# i4screenhsmc.net
KiCad netlist of a schematic drawn in EAGLE
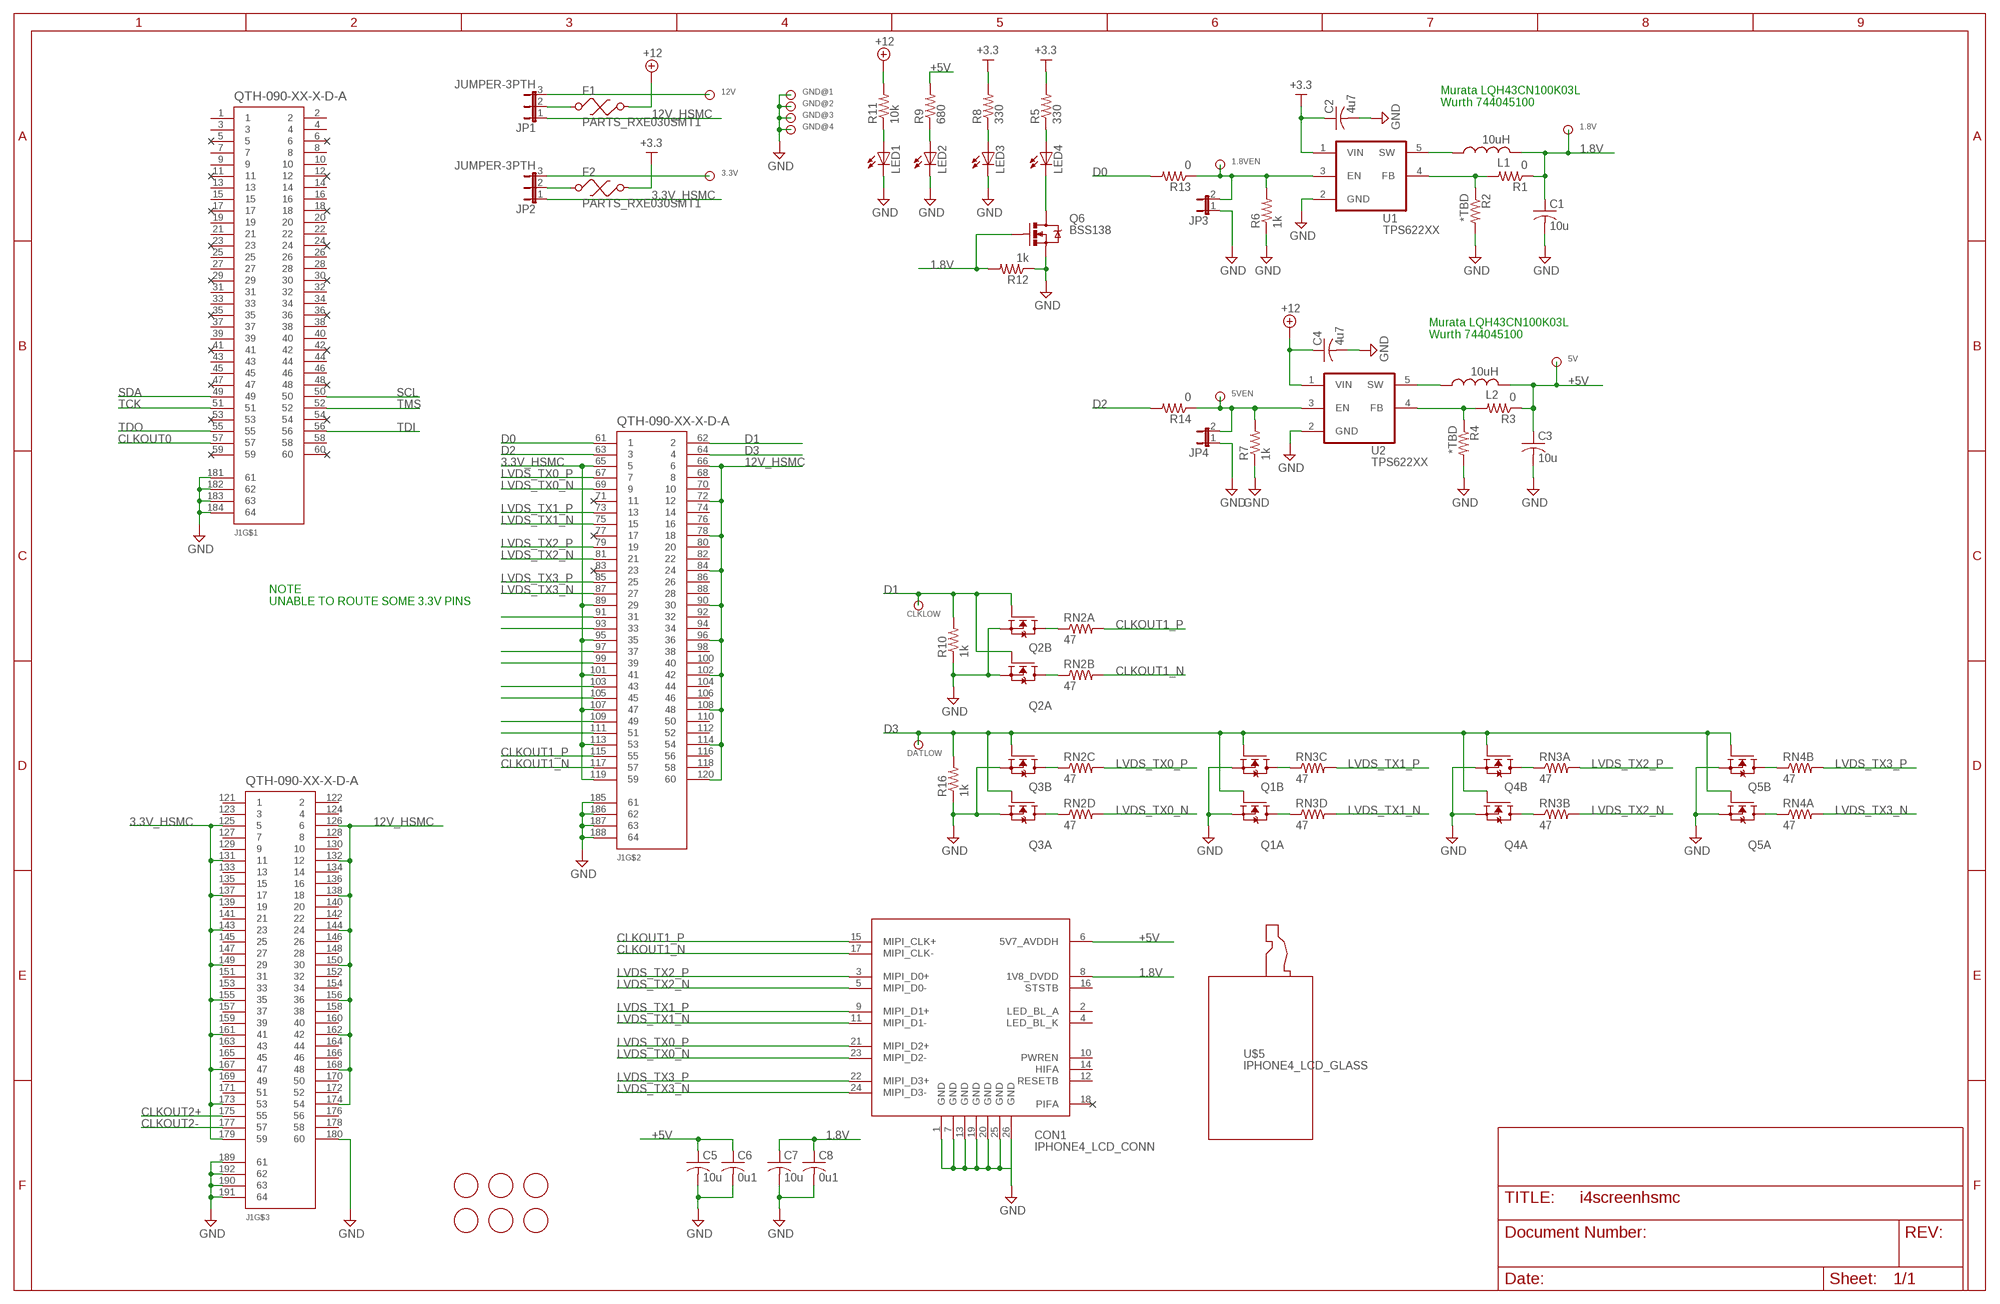
[diagram p0: schematic, sheet 1]

(export (version "E")
  (design (tool "Eeschema 10.0.6"))
  (components
    (comp (ref "1.8V")
      (value "TESTPOINTKEYSTONE_5015")
      (footprint "eagle-import:5015")
      (libsource (lib "eagle-import") (part "TESTPOINTKEYSTONE_5015"))
    )
    (comp (ref "1.8VEN")
      (value "TESTPOINTKEYSTONE_5016")
      (footprint "eagle-import:5016")
      (libsource (lib "eagle-import") (part "TESTPOINTKEYSTONE_5016"))
    )
    (comp (ref "3.3V")
      (value "TESTPOINTBANANA_JACK")
      (footprint "eagle-import:BANANA_JACK")
      (libsource (lib "eagle-import") (part "TESTPOINTBANANA_JACK"))
    )
    (comp (ref "5V")
      (value "TESTPOINTKEYSTONE_5015")
      (footprint "eagle-import:5015")
      (libsource (lib "eagle-import") (part "TESTPOINTKEYSTONE_5015"))
    )
    (comp (ref "5VEN")
      (value "TESTPOINTKEYSTONE_5016")
      (footprint "eagle-import:5016")
      (libsource (lib "eagle-import") (part "TESTPOINTKEYSTONE_5016"))
    )
    (comp (ref "12V")
      (value "TESTPOINTBANANA_JACK")
      (footprint "eagle-import:BANANA_JACK")
      (libsource (lib "eagle-import") (part "TESTPOINTBANANA_JACK"))
    )
    (comp (ref "C1")
      (value "10u")
      (footprint "eagle-import:C0805")
      (libsource (lib "eagle-import") (part "C-USC0805"))
    )
    (comp (ref "C2")
      (value "4u7")
      (footprint "eagle-import:C0805")
      (libsource (lib "eagle-import") (part "C-USC0805"))
    )
    (comp (ref "C3")
      (value "10u")
      (footprint "eagle-import:C0805")
      (libsource (lib "eagle-import") (part "C-USC0805"))
    )
    (comp (ref "C4")
      (value "4u7")
      (footprint "eagle-import:C0805")
      (libsource (lib "eagle-import") (part "C-USC0805"))
    )
    (comp (ref "C5")
      (value "10u")
      (footprint "eagle-import:C0805")
      (libsource (lib "eagle-import") (part "C-USC0805"))
    )
    (comp (ref "C6")
      (value "0u1")
      (footprint "eagle-import:C0805")
      (libsource (lib "eagle-import") (part "C-USC0805"))
    )
    (comp (ref "C7")
      (value "10u")
      (footprint "eagle-import:C0805")
      (libsource (lib "eagle-import") (part "C-USC0805"))
    )
    (comp (ref "C8")
      (value "0u1")
      (footprint "eagle-import:C0805")
      (libsource (lib "eagle-import") (part "C-USC0805"))
    )
    (comp (ref "CLKLOW")
      (value "TESTPOINTKEYSTONE_5016")
      (footprint "eagle-import:5016")
      (libsource (lib "eagle-import") (part "TESTPOINTKEYSTONE_5016"))
    )
    (comp (ref "CON1")
      (value "IPHONE4_LCD_CONN")
      (footprint "eagle-import:AXE4E26124")
      (libsource (lib "eagle-import") (part "IPHONE4_LCD_CONN"))
    )
    (comp (ref "DATLOW")
      (value "TESTPOINTKEYSTONE_5016")
      (footprint "eagle-import:5016")
      (libsource (lib "eagle-import") (part "TESTPOINTKEYSTONE_5016"))
    )
    (comp (ref "F1")
      (value "PARTS_RXE030SMT1")
      (footprint "eagle-import:POLYSWITCH_SMTSMALL")
      (libsource (lib "eagle-import") (part "PARTS_RXE030SMT1"))
    )
    (comp (ref "F2")
      (value "PARTS_RXE030SMT1")
      (footprint "eagle-import:POLYSWITCH_SMTSMALL")
      (libsource (lib "eagle-import") (part "PARTS_RXE030SMT1"))
    )
    (comp (ref "GND@1")
      (value "TESTPOINTBANANA_JACK")
      (footprint "eagle-import:BANANA_JACK")
      (libsource (lib "eagle-import") (part "TESTPOINTBANANA_JACK"))
    )
    (comp (ref "GND@2")
      (value "TESTPOINTBANANA_JACK")
      (footprint "eagle-import:BANANA_JACK")
      (libsource (lib "eagle-import") (part "TESTPOINTBANANA_JACK"))
    )
    (comp (ref "GND@3")
      (value "TESTPOINTKEYSTONE_5015")
      (footprint "eagle-import:5015")
      (libsource (lib "eagle-import") (part "TESTPOINTKEYSTONE_5015"))
    )
    (comp (ref "GND@4")
      (value "TESTPOINTKEYSTONE_5015")
      (footprint "eagle-import:5015")
      (libsource (lib "eagle-import") (part "TESTPOINTKEYSTONE_5015"))
    )
    (comp (ref "J1")
      (value "QTH-090-XX-X-D-A")
      (footprint "eagle-import:QTH-090-XX-X-D-A")
      (libsource (lib "eagle-import") (part "QTH-090-XX-X-D-A"))
    )
    (comp (ref "JP1")
      (value "JUMPER-3PTH")
      (footprint "eagle-import:1X03")
      (libsource (lib "eagle-import") (part "JUMPER-3PTH"))
    )
    (comp (ref "JP2")
      (value "JUMPER-3PTH")
      (footprint "eagle-import:1X03")
      (libsource (lib "eagle-import") (part "JUMPER-3PTH"))
    )
    (comp (ref "JP3")
      (value "JUMPER-2PTH")
      (footprint "eagle-import:1X02")
      (libsource (lib "eagle-import") (part "JUMPER-2PTH"))
    )
    (comp (ref "JP4")
      (value "JUMPER-2PTH")
      (footprint "eagle-import:1X02")
      (libsource (lib "eagle-import") (part "JUMPER-2PTH"))
    )
    (comp (ref "L1")
      (value "10uH")
      (footprint "eagle-import:L1812")
      (libsource (lib "eagle-import") (part "L-USL1812"))
    )
    (comp (ref "L2")
      (value "10uH")
      (footprint "eagle-import:L1812")
      (libsource (lib "eagle-import") (part "L-USL1812"))
    )
    (comp (ref "LED1")
      (value "LEDCHIP-LED0805")
      (footprint "eagle-import:CHIP-LED0805")
      (libsource (lib "eagle-import") (part "LEDCHIP-LED0805"))
    )
    (comp (ref "LED2")
      (value "LEDCHIP-LED0805")
      (footprint "eagle-import:CHIP-LED0805")
      (libsource (lib "eagle-import") (part "LEDCHIP-LED0805"))
    )
    (comp (ref "LED3")
      (value "LEDCHIP-LED0805")
      (footprint "eagle-import:CHIP-LED0805")
      (libsource (lib "eagle-import") (part "LEDCHIP-LED0805"))
    )
    (comp (ref "LED4")
      (value "LEDCHIP-LED0805")
      (footprint "eagle-import:CHIP-LED0805")
      (libsource (lib "eagle-import") (part "LEDCHIP-LED0805"))
    )
    (comp (ref "Q1")
      (value "2N7002SC70-6")
      (footprint "eagle-import:SC70-6")
      (libsource (lib "eagle-import") (part "2N7002SC70-6"))
    )
    (comp (ref "Q2")
      (value "2N7002SC70-6")
      (footprint "eagle-import:SC70-6")
      (libsource (lib "eagle-import") (part "2N7002SC70-6"))
    )
    (comp (ref "Q3")
      (value "2N7002SC70-6")
      (footprint "eagle-import:SC70-6")
      (libsource (lib "eagle-import") (part "2N7002SC70-6"))
    )
    (comp (ref "Q4")
      (value "2N7002SC70-6")
      (footprint "eagle-import:SC70-6")
      (libsource (lib "eagle-import") (part "2N7002SC70-6"))
    )
    (comp (ref "Q5")
      (value "2N7002SC70-6")
      (footprint "eagle-import:SC70-6")
      (libsource (lib "eagle-import") (part "2N7002SC70-6"))
    )
    (comp (ref "Q6")
      (value "BSS138")
      (footprint "eagle-import:SOT23-3")
      (libsource (lib "eagle-import") (part "MOSFET-NCHANNELSMD"))
    )
    (comp (ref "R1")
      (value "0")
      (footprint "eagle-import:R0805")
      (libsource (lib "eagle-import") (part "R-US_R0805"))
    )
    (comp (ref "R2")
      (value "*TBD")
      (footprint "eagle-import:R0805")
      (libsource (lib "eagle-import") (part "R-US_R0805"))
    )
    (comp (ref "R3")
      (value "0")
      (footprint "eagle-import:R0805")
      (libsource (lib "eagle-import") (part "R-US_R0805"))
    )
    (comp (ref "R4")
      (value "*TBD")
      (footprint "eagle-import:R0805")
      (libsource (lib "eagle-import") (part "R-US_R0805"))
    )
    (comp (ref "R5")
      (value "330")
      (footprint "eagle-import:R0805")
      (libsource (lib "eagle-import") (part "R-US_R0805"))
    )
    (comp (ref "R6")
      (value "1k")
      (footprint "eagle-import:R0805")
      (libsource (lib "eagle-import") (part "R-US_R0805"))
    )
    (comp (ref "R7")
      (value "1k")
      (footprint "eagle-import:R0805")
      (libsource (lib "eagle-import") (part "R-US_R0805"))
    )
    (comp (ref "R8")
      (value "330")
      (footprint "eagle-import:R0805")
      (libsource (lib "eagle-import") (part "R-US_R0805"))
    )
    (comp (ref "R9")
      (value "680")
      (footprint "eagle-import:R0805")
      (libsource (lib "eagle-import") (part "R-US_R0805"))
    )
    (comp (ref "R10")
      (value "1k")
      (footprint "eagle-import:R0805")
      (libsource (lib "eagle-import") (part "R-US_R0805"))
    )
    (comp (ref "R11")
      (value "10k")
      (footprint "eagle-import:R0805")
      (libsource (lib "eagle-import") (part "R-US_R0805"))
    )
    (comp (ref "R12")
      (value "1k")
      (footprint "eagle-import:R0805")
      (libsource (lib "eagle-import") (part "R-US_R0805"))
    )
    (comp (ref "R13")
      (value "0")
      (footprint "eagle-import:R0805")
      (libsource (lib "eagle-import") (part "R-US_R0805"))
    )
    (comp (ref "R14")
      (value "0")
      (footprint "eagle-import:R0805")
      (libsource (lib "eagle-import") (part "R-US_R0805"))
    )
    (comp (ref "R16")
      (value "1k")
      (footprint "eagle-import:R0805")
      (libsource (lib "eagle-import") (part "R-US_R0805"))
    )
    (comp (ref "RN2")
      (value "47")
      (footprint "eagle-import:2008")
      (libsource (lib "eagle-import") (part "RES_NETWORK0805"))
    )
    (comp (ref "RN3")
      (value "47")
      (footprint "eagle-import:2008")
      (libsource (lib "eagle-import") (part "RES_NETWORK0805"))
    )
    (comp (ref "RN4")
      (value "47")
      (footprint "eagle-import:2008")
      (libsource (lib "eagle-import") (part "RES_NETWORK0805"))
    )
    (comp (ref "U$1")
      (value "MOUNTING_HOLE125")
      (footprint "eagle-import:HOLE_MTG_125")
      (libsource (lib "eagle-import") (part "MOUNTING_HOLE125"))
    )
    (comp (ref "U$2")
      (value "MOUNTING_HOLE125")
      (footprint "eagle-import:HOLE_MTG_125")
      (libsource (lib "eagle-import") (part "MOUNTING_HOLE125"))
    )
    (comp (ref "U$3")
      (value "MOUNTING_HOLE125")
      (footprint "eagle-import:HOLE_MTG_125")
      (libsource (lib "eagle-import") (part "MOUNTING_HOLE125"))
    )
    (comp (ref "U$4")
      (value "MOUNTING_HOLE125")
      (footprint "eagle-import:HOLE_MTG_125")
      (libsource (lib "eagle-import") (part "MOUNTING_HOLE125"))
    )
    (comp (ref "U$5")
      (value "IPHONE4_LCD_GLASS")
      (footprint "eagle-import:IPHONE4_LCD")
      (libsource (lib "eagle-import") (part "IPHONE4_LCD_GLASS"))
    )
    (comp (ref "U$48")
      (value "MOUNTING_HOLE125")
      (footprint "eagle-import:HOLE_MTG_125")
      (libsource (lib "eagle-import") (part "MOUNTING_HOLE125"))
    )
    (comp (ref "U$49")
      (value "MOUNTING_HOLE125")
      (footprint "eagle-import:HOLE_MTG_125")
      (libsource (lib "eagle-import") (part "MOUNTING_HOLE125"))
    )
    (comp (ref "U1")
      (value "TPS622XX")
      (footprint "eagle-import:SOT23-5")
      (libsource (lib "eagle-import") (part "TPS622XX"))
    )
    (comp (ref "U2")
      (value "TPS622XX")
      (footprint "eagle-import:SOT23-5")
      (libsource (lib "eagle-import") (part "TPS622XX"))
    )
  )
  (nets
    (net (code "1") (name "+3.3") (class "Default")
      (node (ref "C2") (pin "1") (pinfunction "1_1") (pintype "passive"))
      (node (ref "F2") (pin "P$2") (pinfunction "2_P$2") (pintype "passive"))
      (node (ref "R5") (pin "2") (pinfunction "2_2") (pintype "passive"))
      (node (ref "R8") (pin "2") (pinfunction "2_2") (pintype "passive"))
      (node (ref "U1") (pin "1") (pinfunction "VIN_1") (pintype "passive"))
    )
    (net (code "2") (name "+12") (class "Default")
      (node (ref "C4") (pin "1") (pinfunction "1_1") (pintype "passive"))
      (node (ref "F1") (pin "P$2") (pinfunction "2_P$2") (pintype "passive"))
      (node (ref "R11") (pin "2") (pinfunction "2_2") (pintype "passive"))
      (node (ref "U2") (pin "1") (pinfunction "VIN_1") (pintype "passive"))
    )
    (net (code "3") (name "/+5V") (class "Default")
      (node (ref "5V") (pin "P$1") (pinfunction "1_P$1") (pintype "passive"))
      (node (ref "C3") (pin "1") (pinfunction "1_1") (pintype "passive"))
      (node (ref "C5") (pin "1") (pinfunction "1_1") (pintype "passive"))
      (node (ref "C6") (pin "1") (pinfunction "1_1") (pintype "passive"))
      (node (ref "CON1") (pin "6") (pinfunction "5V7_AVDDH_6") (pintype "power_in"))
      (node (ref "L2") (pin "2") (pinfunction "2_2") (pintype "passive"))
      (node (ref "R3") (pin "1") (pinfunction "1_1") (pintype "passive"))
      (node (ref "R9") (pin "2") (pinfunction "2_2") (pintype "passive"))
    )
    (net (code "4") (name "/1.8V") (class "Default")
      (node (ref "1.8V") (pin "P$1") (pinfunction "1_P$1") (pintype "passive"))
      (node (ref "C1") (pin "1") (pinfunction "1_1") (pintype "passive"))
      (node (ref "C7") (pin "1") (pinfunction "1_1") (pintype "passive"))
      (node (ref "C8") (pin "1") (pinfunction "1_1") (pintype "passive"))
      (node (ref "CON1") (pin "8") (pinfunction "1V8_DVDD_8") (pintype "power_in"))
      (node (ref "L1") (pin "2") (pinfunction "2_2") (pintype "passive"))
      (node (ref "Q6") (pin "1") (pinfunction "G_1") (pintype "passive"))
      (node (ref "R1") (pin "1") (pinfunction "1_1") (pintype "passive"))
      (node (ref "R12") (pin "2") (pinfunction "2_2") (pintype "passive"))
    )
    (net (code "5") (name "/3.3V_HSMC") (class "Default")
      (node (ref "J1") (pin "101") (pinfunction "41_101") (pintype "bidirectional"))
      (node (ref "J1") (pin "107") (pinfunction "47_107") (pintype "bidirectional"))
      (node (ref "J1") (pin "113") (pinfunction "53_113") (pintype "bidirectional"))
      (node (ref "J1") (pin "119") (pinfunction "59_119") (pintype "bidirectional"))
      (node (ref "J1") (pin "125") (pinfunction "5_125") (pintype "bidirectional"))
      (node (ref "J1") (pin "131") (pinfunction "11_131") (pintype "bidirectional"))
      (node (ref "J1") (pin "137") (pinfunction "17_137") (pintype "bidirectional"))
      (node (ref "J1") (pin "143") (pinfunction "23_143") (pintype "bidirectional"))
      (node (ref "J1") (pin "149") (pinfunction "29_149") (pintype "bidirectional"))
      (node (ref "J1") (pin "155") (pinfunction "35_155") (pintype "bidirectional"))
      (node (ref "J1") (pin "161") (pinfunction "41_161") (pintype "bidirectional"))
      (node (ref "J1") (pin "167") (pinfunction "47_167") (pintype "bidirectional"))
      (node (ref "J1") (pin "173") (pinfunction "53_173") (pintype "bidirectional"))
      (node (ref "J1") (pin "179") (pinfunction "59_179") (pintype "bidirectional"))
      (node (ref "J1") (pin "65") (pinfunction "5_65") (pintype "bidirectional"))
      (node (ref "J1") (pin "89") (pinfunction "29_89") (pintype "bidirectional"))
      (node (ref "J1") (pin "95") (pinfunction "35_95") (pintype "bidirectional"))
      (node (ref "JP2") (pin "1") (pinfunction "1_1") (pintype "passive"))
    )
    (net (code "6") (name "/12V_HSMC") (class "Default")
      (node (ref "J1") (pin "102") (pinfunction "42_102") (pintype "bidirectional"))
      (node (ref "J1") (pin "108") (pinfunction "48_108") (pintype "bidirectional"))
      (node (ref "J1") (pin "114") (pinfunction "54_114") (pintype "bidirectional"))
      (node (ref "J1") (pin "120") (pinfunction "60_120") (pintype "bidirectional"))
      (node (ref "J1") (pin "126") (pinfunction "6_126") (pintype "bidirectional"))
      (node (ref "J1") (pin "132") (pinfunction "12_132") (pintype "bidirectional"))
      (node (ref "J1") (pin "138") (pinfunction "18_138") (pintype "bidirectional"))
      (node (ref "J1") (pin "144") (pinfunction "24_144") (pintype "bidirectional"))
      (node (ref "J1") (pin "150") (pinfunction "30_150") (pintype "bidirectional"))
      (node (ref "J1") (pin "156") (pinfunction "36_156") (pintype "bidirectional"))
      (node (ref "J1") (pin "162") (pinfunction "42_162") (pintype "bidirectional"))
      (node (ref "J1") (pin "168") (pinfunction "48_168") (pintype "bidirectional"))
      (node (ref "J1") (pin "174") (pinfunction "54_174") (pintype "bidirectional"))
      (node (ref "J1") (pin "66") (pinfunction "6_66") (pintype "bidirectional"))
      (node (ref "J1") (pin "72") (pinfunction "12_72") (pintype "bidirectional"))
      (node (ref "J1") (pin "78") (pinfunction "18_78") (pintype "bidirectional"))
      (node (ref "J1") (pin "84") (pinfunction "24_84") (pintype "bidirectional"))
      (node (ref "J1") (pin "90") (pinfunction "30_90") (pintype "bidirectional"))
      (node (ref "J1") (pin "96") (pinfunction "36_96") (pintype "bidirectional"))
      (node (ref "JP1") (pin "1") (pinfunction "1_1") (pintype "passive"))
    )
    (net (code "7") (name "/CLKOUT0") (class "Default")
      (node (ref "J1") (pin "57") (pinfunction "57_57") (pintype "bidirectional"))
    )
    (net (code "8") (name "/CLKOUT1_N") (class "Default")
      (node (ref "CON1") (pin "17") (pinfunction "MIPI_CLK-_17") (pintype "input"))
      (node (ref "J1") (pin "117") (pinfunction "57_117") (pintype "bidirectional"))
      (node (ref "RN2") (pin "7") (pinfunction "2_7") (pintype "passive"))
    )
    (net (code "9") (name "/CLKOUT1_P") (class "Default")
      (node (ref "CON1") (pin "15") (pinfunction "MIPI_CLK+_15") (pintype "input"))
      (node (ref "J1") (pin "115") (pinfunction "55_115") (pintype "bidirectional"))
      (node (ref "RN2") (pin "8") (pinfunction "2_8") (pintype "passive"))
    )
    (net (code "10") (name "/CLKOUT2+") (class "Default")
      (node (ref "J1") (pin "175") (pinfunction "55_175") (pintype "bidirectional"))
    )
    (net (code "11") (name "/CLKOUT2-") (class "Default")
      (node (ref "J1") (pin "177") (pinfunction "57_177") (pintype "bidirectional"))
    )
    (net (code "12") (name "/D0") (class "Default")
      (node (ref "J1") (pin "61") (pinfunction "1_61") (pintype "bidirectional"))
      (node (ref "R13") (pin "2") (pinfunction "2_2") (pintype "passive"))
    )
    (net (code "13") (name "/D1") (class "Default")
      (node (ref "CLKLOW") (pin "P$1") (pinfunction "1_P$1") (pintype "passive"))
      (node (ref "J1") (pin "62") (pinfunction "2_62") (pintype "bidirectional"))
      (node (ref "Q2") (pin "2") (pinfunction "G_2") (pintype "passive"))
      (node (ref "Q2") (pin "5") (pinfunction "G_5") (pintype "passive"))
      (node (ref "R10") (pin "2") (pinfunction "2_2") (pintype "passive"))
    )
    (net (code "14") (name "/D2") (class "Default")
      (node (ref "J1") (pin "63") (pinfunction "3_63") (pintype "bidirectional"))
      (node (ref "R14") (pin "2") (pinfunction "2_2") (pintype "passive"))
    )
    (net (code "15") (name "/D3") (class "Default")
      (node (ref "DATLOW") (pin "P$1") (pinfunction "1_P$1") (pintype "passive"))
      (node (ref "J1") (pin "64") (pinfunction "4_64") (pintype "bidirectional"))
      (node (ref "Q1") (pin "2") (pinfunction "G_2") (pintype "passive"))
      (node (ref "Q1") (pin "5") (pinfunction "G_5") (pintype "passive"))
      (node (ref "Q3") (pin "2") (pinfunction "G_2") (pintype "passive"))
      (node (ref "Q3") (pin "5") (pinfunction "G_5") (pintype "passive"))
      (node (ref "Q4") (pin "2") (pinfunction "G_2") (pintype "passive"))
      (node (ref "Q4") (pin "5") (pinfunction "G_5") (pintype "passive"))
      (node (ref "Q5") (pin "2") (pinfunction "G_2") (pintype "passive"))
      (node (ref "Q5") (pin "5") (pinfunction "G_5") (pintype "passive"))
      (node (ref "R16") (pin "2") (pinfunction "2_2") (pintype "passive"))
    )
    (net (code "16") (name "/LVDS_TX0_N") (class "Default")
      (node (ref "CON1") (pin "23") (pinfunction "MIPI_D2-_23") (pintype "input"))
      (node (ref "J1") (pin "69") (pinfunction "9_69") (pintype "bidirectional"))
      (node (ref "RN2") (pin "5") (pinfunction "2_5") (pintype "passive"))
    )
    (net (code "17") (name "/LVDS_TX0_P") (class "Default")
      (node (ref "CON1") (pin "21") (pinfunction "MIPI_D2+_21") (pintype "input"))
      (node (ref "J1") (pin "67") (pinfunction "7_67") (pintype "bidirectional"))
      (node (ref "RN2") (pin "6") (pinfunction "2_6") (pintype "passive"))
    )
    (net (code "18") (name "/LVDS_TX1_N") (class "Default")
      (node (ref "CON1") (pin "11") (pinfunction "MIPI_D1-_11") (pintype "input"))
      (node (ref "J1") (pin "75") (pinfunction "15_75") (pintype "bidirectional"))
      (node (ref "RN3") (pin "5") (pinfunction "2_5") (pintype "passive"))
    )
    (net (code "19") (name "/LVDS_TX1_P") (class "Default")
      (node (ref "CON1") (pin "9") (pinfunction "MIPI_D1+_9") (pintype "input"))
      (node (ref "J1") (pin "73") (pinfunction "13_73") (pintype "bidirectional"))
      (node (ref "RN3") (pin "6") (pinfunction "2_6") (pintype "passive"))
    )
    (net (code "20") (name "/LVDS_TX2_N") (class "Default")
      (node (ref "CON1") (pin "5") (pinfunction "MIPI_D0-_5") (pintype "input"))
      (node (ref "J1") (pin "81") (pinfunction "21_81") (pintype "bidirectional"))
      (node (ref "RN3") (pin "7") (pinfunction "2_7") (pintype "passive"))
    )
    (net (code "21") (name "/LVDS_TX2_P") (class "Default")
      (node (ref "CON1") (pin "3") (pinfunction "MIPI_D0+_3") (pintype "input"))
      (node (ref "J1") (pin "79") (pinfunction "19_79") (pintype "bidirectional"))
      (node (ref "RN3") (pin "8") (pinfunction "2_8") (pintype "passive"))
    )
    (net (code "22") (name "/LVDS_TX3_N") (class "Default")
      (node (ref "CON1") (pin "24") (pinfunction "MIPI_D3-_24") (pintype "input"))
      (node (ref "J1") (pin "87") (pinfunction "27_87") (pintype "bidirectional"))
      (node (ref "RN4") (pin "8") (pinfunction "2_8") (pintype "passive"))
    )
    (net (code "23") (name "/LVDS_TX3_P") (class "Default")
      (node (ref "CON1") (pin "22") (pinfunction "MIPI_D3+_22") (pintype "input"))
      (node (ref "J1") (pin "85") (pinfunction "25_85") (pintype "bidirectional"))
      (node (ref "RN4") (pin "7") (pinfunction "2_7") (pintype "passive"))
    )
    (net (code "24") (name "/SCL") (class "Default")
      (node (ref "J1") (pin "50") (pinfunction "50_50") (pintype "bidirectional"))
    )
    (net (code "25") (name "/SDA") (class "Default")
      (node (ref "J1") (pin "49") (pinfunction "49_49") (pintype "bidirectional"))
    )
    (net (code "26") (name "/TCK") (class "Default")
      (node (ref "J1") (pin "51") (pinfunction "51_51") (pintype "bidirectional"))
    )
    (net (code "27") (name "/TDI") (class "Default")
      (node (ref "J1") (pin "56") (pinfunction "56_56") (pintype "bidirectional"))
    )
    (net (code "28") (name "/TDO") (class "Default")
      (node (ref "J1") (pin "55") (pinfunction "55_55") (pintype "bidirectional"))
    )
    (net (code "29") (name "/TMS") (class "Default")
      (node (ref "J1") (pin "52") (pinfunction "52_52") (pintype "bidirectional"))
    )
    (net (code "30") (name "GND") (class "Default")
      (node (ref "C1") (pin "2") (pinfunction "2_2") (pintype "passive"))
      (node (ref "C2") (pin "2") (pinfunction "2_2") (pintype "passive"))
      (node (ref "C3") (pin "2") (pinfunction "2_2") (pintype "passive"))
      (node (ref "C4") (pin "2") (pinfunction "2_2") (pintype "passive"))
      (node (ref "C5") (pin "2") (pinfunction "2_2") (pintype "passive"))
      (node (ref "C6") (pin "2") (pinfunction "2_2") (pintype "passive"))
      (node (ref "C7") (pin "2") (pinfunction "2_2") (pintype "passive"))
      (node (ref "C8") (pin "2") (pinfunction "2_2") (pintype "passive"))
      (node (ref "CON1") (pin "1") (pinfunction "GND_1") (pintype "power_in"))
      (node (ref "CON1") (pin "13") (pinfunction "GND_13") (pintype "power_in"))
      (node (ref "CON1") (pin "19") (pinfunction "GND_19") (pintype "power_in"))
      (node (ref "CON1") (pin "20") (pinfunction "GND_20") (pintype "power_in"))
      (node (ref "CON1") (pin "25") (pinfunction "GND_25") (pintype "power_in"))
      (node (ref "CON1") (pin "26") (pinfunction "GND_26") (pintype "power_in"))
      (node (ref "CON1") (pin "7") (pinfunction "GND_7") (pintype "power_in"))
      (node (ref "GND@1") (pin "1") (pinfunction "1_1") (pintype "passive"))
      (node (ref "GND@2") (pin "1") (pinfunction "1_1") (pintype "passive"))
      (node (ref "GND@3") (pin "P$1") (pinfunction "1_P$1") (pintype "passive"))
      (node (ref "GND@4") (pin "P$1") (pinfunction "1_P$1") (pintype "passive"))
      (node (ref "J1") (pin "180") (pinfunction "60_180") (pintype "bidirectional"))
      (node (ref "J1") (pin "181") (pinfunction "61_181") (pintype "power_in"))
      (node (ref "J1") (pin "182") (pinfunction "62_182") (pintype "power_in"))
      (node (ref "J1") (pin "183") (pinfunction "63_183") (pintype "power_in"))
      (node (ref "J1") (pin "184") (pinfunction "64_184") (pintype "power_in"))
      (node (ref "J1") (pin "185") (pinfunction "61_185") (pintype "power_in"))
      (node (ref "J1") (pin "186") (pinfunction "62_186") (pintype "power_in"))
      (node (ref "J1") (pin "187") (pinfunction "63_187") (pintype "power_in"))
      (node (ref "J1") (pin "188") (pinfunction "64_188") (pintype "power_in"))
      (node (ref "J1") (pin "189") (pinfunction "61_189") (pintype "power_in"))
      (node (ref "J1") (pin "190") (pinfunction "63_190") (pintype "power_in"))
      (node (ref "J1") (pin "191") (pinfunction "64_191") (pintype "power_in"))
      (node (ref "J1") (pin "192") (pinfunction "62_192") (pintype "power_in"))
      (node (ref "JP3") (pin "1") (pinfunction "1_1") (pintype "passive"))
      (node (ref "JP4") (pin "1") (pinfunction "1_1") (pintype "passive"))
      (node (ref "LED1") (pin "C") (pinfunction "C_C") (pintype "passive"))
      (node (ref "LED2") (pin "C") (pinfunction "C_C") (pintype "passive"))
      (node (ref "LED3") (pin "C") (pinfunction "C_C") (pintype "passive"))
      (node (ref "Q1") (pin "1") (pinfunction "S_1") (pintype "passive"))
      (node (ref "Q1") (pin "4") (pinfunction "S_4") (pintype "passive"))
      (node (ref "Q2") (pin "1") (pinfunction "S_1") (pintype "passive"))
      (node (ref "Q2") (pin "4") (pinfunction "S_4") (pintype "passive"))
      (node (ref "Q3") (pin "1") (pinfunction "S_1") (pintype "passive"))
      (node (ref "Q3") (pin "4") (pinfunction "S_4") (pintype "passive"))
      (node (ref "Q4") (pin "1") (pinfunction "S_1") (pintype "passive"))
      (node (ref "Q4") (pin "4") (pinfunction "S_4") (pintype "passive"))
      (node (ref "Q5") (pin "1") (pinfunction "S_1") (pintype "passive"))
      (node (ref "Q5") (pin "4") (pinfunction "S_4") (pintype "passive"))
      (node (ref "Q6") (pin "2") (pinfunction "S_2") (pintype "passive"))
      (node (ref "R10") (pin "1") (pinfunction "1_1") (pintype "passive"))
      (node (ref "R12") (pin "1") (pinfunction "1_1") (pintype "passive"))
      (node (ref "R16") (pin "1") (pinfunction "1_1") (pintype "passive"))
      (node (ref "R2") (pin "2") (pinfunction "2_2") (pintype "passive"))
      (node (ref "R4") (pin "2") (pinfunction "2_2") (pintype "passive"))
      (node (ref "R6") (pin "1") (pinfunction "1_1") (pintype "passive"))
      (node (ref "R7") (pin "1") (pinfunction "1_1") (pintype "passive"))
      (node (ref "U1") (pin "2") (pinfunction "GND_2") (pintype "power_in"))
      (node (ref "U2") (pin "2") (pinfunction "GND_2") (pintype "power_in"))
    )
    (net (code "31") (name "Net-(1.8VEN-1)") (class "Default")
      (node (ref "1.8VEN") (pin "P$1") (pinfunction "1_P$1") (pintype "passive"))
      (node (ref "JP3") (pin "2") (pinfunction "2_2") (pintype "passive"))
      (node (ref "R13") (pin "1") (pinfunction "1_1") (pintype "passive"))
      (node (ref "R6") (pin "2") (pinfunction "2_2") (pintype "passive"))
      (node (ref "U1") (pin "3") (pinfunction "EN_3") (pintype "input"))
    )
    (net (code "32") (name "Net-(3.3V-Pad1)") (class "Default")
      (node (ref "3.3V") (pin "1") (pinfunction "1_1") (pintype "passive"))
      (node (ref "JP2") (pin "3") (pinfunction "3_3") (pintype "passive"))
    )
    (net (code "33") (name "Net-(5VEN-1)") (class "Default")
      (node (ref "5VEN") (pin "P$1") (pinfunction "1_P$1") (pintype "passive"))
      (node (ref "JP4") (pin "2") (pinfunction "2_2") (pintype "passive"))
      (node (ref "R14") (pin "1") (pinfunction "1_1") (pintype "passive"))
      (node (ref "R7") (pin "2") (pinfunction "2_2") (pintype "passive"))
      (node (ref "U2") (pin "3") (pinfunction "EN_3") (pintype "input"))
    )
    (net (code "34") (name "Net-(12V-Pad1)") (class "Default")
      (node (ref "12V") (pin "1") (pinfunction "1_1") (pintype "passive"))
      (node (ref "JP1") (pin "3") (pinfunction "3_3") (pintype "passive"))
    )
    (net (code "35") (name "Net-(F1-1)") (class "Default")
      (node (ref "F1") (pin "P$1") (pinfunction "1_P$1") (pintype "passive"))
      (node (ref "JP1") (pin "2") (pinfunction "2_2") (pintype "passive"))
    )
    (net (code "36") (name "Net-(F2-1)") (class "Default")
      (node (ref "F2") (pin "P$1") (pinfunction "1_P$1") (pintype "passive"))
      (node (ref "JP2") (pin "2") (pinfunction "2_2") (pintype "passive"))
    )
    (net (code "37") (name "Net-(LED1-PadA)") (class "Default")
      (node (ref "LED1") (pin "A") (pinfunction "A_A") (pintype "passive"))
      (node (ref "R11") (pin "1") (pinfunction "1_1") (pintype "passive"))
    )
    (net (code "38") (name "Net-(LED2-PadA)") (class "Default")
      (node (ref "LED2") (pin "A") (pinfunction "A_A") (pintype "passive"))
      (node (ref "R9") (pin "1") (pinfunction "1_1") (pintype "passive"))
    )
    (net (code "39") (name "Net-(LED3-PadA)") (class "Default")
      (node (ref "LED3") (pin "A") (pinfunction "A_A") (pintype "passive"))
      (node (ref "R8") (pin "1") (pinfunction "1_1") (pintype "passive"))
    )
    (net (code "40") (name "Net-(LED4-PadA)") (class "Default")
      (node (ref "LED4") (pin "A") (pinfunction "A_A") (pintype "passive"))
      (node (ref "R5") (pin "1") (pinfunction "1_1") (pintype "passive"))
    )
    (net (code "41") (name "Net-(Q1A-D)") (class "Default")
      (node (ref "Q1") (pin "3") (pinfunction "D_3") (pintype "passive"))
      (node (ref "RN3") (pin "4") (pinfunction "1_4") (pintype "passive"))
    )
    (net (code "42") (name "Net-(Q1B-D)") (class "Default")
      (node (ref "Q1") (pin "6") (pinfunction "D_6") (pintype "passive"))
      (node (ref "RN3") (pin "3") (pinfunction "1_3") (pintype "passive"))
    )
    (net (code "43") (name "Net-(Q2A-D)") (class "Default")
      (node (ref "Q2") (pin "3") (pinfunction "D_3") (pintype "passive"))
      (node (ref "RN2") (pin "2") (pinfunction "1_2") (pintype "passive"))
    )
    (net (code "44") (name "Net-(Q2B-D)") (class "Default")
      (node (ref "Q2") (pin "6") (pinfunction "D_6") (pintype "passive"))
      (node (ref "RN2") (pin "1") (pinfunction "1_1") (pintype "passive"))
    )
    (net (code "45") (name "Net-(Q3A-D)") (class "Default")
      (node (ref "Q3") (pin "3") (pinfunction "D_3") (pintype "passive"))
      (node (ref "RN2") (pin "4") (pinfunction "1_4") (pintype "passive"))
    )
    (net (code "46") (name "Net-(Q3B-D)") (class "Default")
      (node (ref "Q3") (pin "6") (pinfunction "D_6") (pintype "passive"))
      (node (ref "RN2") (pin "3") (pinfunction "1_3") (pintype "passive"))
    )
    (net (code "47") (name "Net-(Q4A-D)") (class "Default")
      (node (ref "Q4") (pin "3") (pinfunction "D_3") (pintype "passive"))
      (node (ref "RN3") (pin "2") (pinfunction "1_2") (pintype "passive"))
    )
    (net (code "48") (name "Net-(Q4B-D)") (class "Default")
      (node (ref "Q4") (pin "6") (pinfunction "D_6") (pintype "passive"))
      (node (ref "RN3") (pin "1") (pinfunction "1_1") (pintype "passive"))
    )
    (net (code "49") (name "Net-(Q5A-D)") (class "Default")
      (node (ref "Q5") (pin "3") (pinfunction "D_3") (pintype "passive"))
      (node (ref "RN4") (pin "1") (pinfunction "1_1") (pintype "passive"))
    )
    (net (code "50") (name "Net-(Q5B-D)") (class "Default")
      (node (ref "Q5") (pin "6") (pinfunction "D_6") (pintype "passive"))
      (node (ref "RN4") (pin "2") (pinfunction "1_2") (pintype "passive"))
    )
    (net (code "51") (name "Net-(Q6-D)") (class "Default")
      (node (ref "LED4") (pin "C") (pinfunction "C_C") (pintype "passive"))
      (node (ref "Q6") (pin "3") (pinfunction "D_3") (pintype "passive"))
    )
    (net (code "52") (name "Net-(U1-FB)") (class "Default")
      (node (ref "R1") (pin "2") (pinfunction "2_2") (pintype "passive"))
      (node (ref "R2") (pin "1") (pinfunction "1_1") (pintype "passive"))
      (node (ref "U1") (pin "4") (pinfunction "FB_4") (pintype "passive"))
    )
    (net (code "53") (name "Net-(U1-SW)") (class "Default")
      (node (ref "L1") (pin "1") (pinfunction "1_1") (pintype "passive"))
      (node (ref "U1") (pin "5") (pinfunction "SW_5") (pintype "passive"))
    )
    (net (code "54") (name "Net-(U2-FB)") (class "Default")
      (node (ref "R3") (pin "2") (pinfunction "2_2") (pintype "passive"))
      (node (ref "R4") (pin "1") (pinfunction "1_1") (pintype "passive"))
      (node (ref "U2") (pin "4") (pinfunction "FB_4") (pintype "passive"))
    )
    (net (code "55") (name "Net-(U2-SW)") (class "Default")
      (node (ref "L2") (pin "1") (pinfunction "1_1") (pintype "passive"))
      (node (ref "U2") (pin "5") (pinfunction "SW_5") (pintype "passive"))
    )
    (net (code "56") (name "unconnected-(CON1-HIFA-Pad14)") (class "Default")
      (node (ref "CON1") (pin "14") (pinfunction "HIFA_14") (pintype "input"))
    )
    (net (code "57") (name "unconnected-(CON1-LED_BL_A-Pad2)") (class "Default")
      (node (ref "CON1") (pin "2") (pinfunction "LED_BL_A_2") (pintype "passive"))
    )
    (net (code "58") (name "unconnected-(CON1-LED_BL_K-Pad4)") (class "Default")
      (node (ref "CON1") (pin "4") (pinfunction "LED_BL_K_4") (pintype "passive"))
    )
    (net (code "59") (name "unconnected-(CON1-PIFA-Pad18)") (class "Default")
      (node (ref "CON1") (pin "18") (pinfunction "PIFA_18") (pintype "input"))
    )
    (net (code "60") (name "unconnected-(CON1-PWREN-Pad10)") (class "Default")
      (node (ref "CON1") (pin "10") (pinfunction "PWREN_10") (pintype "input"))
    )
    (net (code "61") (name "unconnected-(CON1-RESETB-Pad12)") (class "Default")
      (node (ref "CON1") (pin "12") (pinfunction "RESETB_12") (pintype "input"))
    )
    (net (code "62") (name "unconnected-(CON1-STSTB-Pad16)") (class "Default")
      (node (ref "CON1") (pin "16") (pinfunction "STSTB_16") (pintype "input"))
    )
    (net (code "63") (name "unconnected-(J1-Pad1)") (class "Default")
      (node (ref "J1") (pin "1") (pinfunction "1_1") (pintype "bidirectional"))
    )
    (net (code "64") (name "unconnected-(J1-Pad2)") (class "Default")
      (node (ref "J1") (pin "2") (pinfunction "2_2") (pintype "bidirectional"))
    )
    (net (code "65") (name "unconnected-(J1-Pad3)") (class "Default")
      (node (ref "J1") (pin "3") (pinfunction "3_3") (pintype "bidirectional"))
    )
    (net (code "66") (name "unconnected-(J1-Pad4)") (class "Default")
      (node (ref "J1") (pin "4") (pinfunction "4_4") (pintype "bidirectional"))
    )
    (net (code "67") (name "unconnected-(J1-Pad5)") (class "Default")
      (node (ref "J1") (pin "5") (pinfunction "5_5") (pintype "bidirectional"))
    )
    (net (code "68") (name "unconnected-(J1-Pad6)") (class "Default")
      (node (ref "J1") (pin "6") (pinfunction "6_6") (pintype "bidirectional"))
    )
    (net (code "69") (name "unconnected-(J1-Pad7)") (class "Default")
      (node (ref "J1") (pin "7") (pinfunction "7_7") (pintype "bidirectional"))
    )
    (net (code "70") (name "unconnected-(J1-Pad8)") (class "Default")
      (node (ref "J1") (pin "8") (pinfunction "8_8") (pintype "bidirectional"))
    )
    (net (code "71") (name "unconnected-(J1-Pad9)") (class "Default")
      (node (ref "J1") (pin "9") (pinfunction "9_9") (pintype "bidirectional"))
    )
    (net (code "72") (name "unconnected-(J1-Pad10)") (class "Default")
      (node (ref "J1") (pin "10") (pinfunction "10_10") (pintype "bidirectional"))
    )
    (net (code "73") (name "unconnected-(J1-Pad11)") (class "Default")
      (node (ref "J1") (pin "11") (pinfunction "11_11") (pintype "bidirectional"))
    )
    (net (code "74") (name "unconnected-(J1-Pad12)") (class "Default")
      (node (ref "J1") (pin "12") (pinfunction "12_12") (pintype "bidirectional"))
    )
    (net (code "75") (name "unconnected-(J1-Pad13)") (class "Default")
      (node (ref "J1") (pin "13") (pinfunction "13_13") (pintype "bidirectional"))
    )
    (net (code "76") (name "unconnected-(J1-Pad14)") (class "Default")
      (node (ref "J1") (pin "14") (pinfunction "14_14") (pintype "bidirectional"))
    )
    (net (code "77") (name "unconnected-(J1-Pad15)") (class "Default")
      (node (ref "J1") (pin "15") (pinfunction "15_15") (pintype "bidirectional"))
    )
    (net (code "78") (name "unconnected-(J1-Pad16)") (class "Default")
      (node (ref "J1") (pin "16") (pinfunction "16_16") (pintype "bidirectional"))
    )
    (net (code "79") (name "unconnected-(J1-Pad17)") (class "Default")
      (node (ref "J1") (pin "17") (pinfunction "17_17") (pintype "bidirectional"))
    )
    (net (code "80") (name "unconnected-(J1-Pad18)") (class "Default")
      (node (ref "J1") (pin "18") (pinfunction "18_18") (pintype "bidirectional"))
    )
    (net (code "81") (name "unconnected-(J1-Pad19)") (class "Default")
      (node (ref "J1") (pin "19") (pinfunction "19_19") (pintype "bidirectional"))
    )
    (net (code "82") (name "unconnected-(J1-Pad20)") (class "Default")
      (node (ref "J1") (pin "20") (pinfunction "20_20") (pintype "bidirectional"))
    )
    (net (code "83") (name "unconnected-(J1-Pad21)") (class "Default")
      (node (ref "J1") (pin "21") (pinfunction "21_21") (pintype "bidirectional"))
    )
    (net (code "84") (name "unconnected-(J1-Pad22)") (class "Default")
      (node (ref "J1") (pin "22") (pinfunction "22_22") (pintype "bidirectional"))
    )
    (net (code "85") (name "unconnected-(J1-Pad23)") (class "Default")
      (node (ref "J1") (pin "23") (pinfunction "23_23") (pintype "bidirectional"))
    )
    (net (code "86") (name "unconnected-(J1-Pad24)") (class "Default")
      (node (ref "J1") (pin "24") (pinfunction "24_24") (pintype "bidirectional"))
    )
    (net (code "87") (name "unconnected-(J1-Pad25)") (class "Default")
      (node (ref "J1") (pin "25") (pinfunction "25_25") (pintype "bidirectional"))
    )
    (net (code "88") (name "unconnected-(J1-Pad26)") (class "Default")
      (node (ref "J1") (pin "26") (pinfunction "26_26") (pintype "bidirectional"))
    )
    (net (code "89") (name "unconnected-(J1-Pad27)") (class "Default")
      (node (ref "J1") (pin "27") (pinfunction "27_27") (pintype "bidirectional"))
    )
    (net (code "90") (name "unconnected-(J1-Pad28)") (class "Default")
      (node (ref "J1") (pin "28") (pinfunction "28_28") (pintype "bidirectional"))
    )
    (net (code "91") (name "unconnected-(J1-Pad29)") (class "Default")
      (node (ref "J1") (pin "29") (pinfunction "29_29") (pintype "bidirectional"))
    )
    (net (code "92") (name "unconnected-(J1-Pad30)") (class "Default")
      (node (ref "J1") (pin "30") (pinfunction "30_30") (pintype "bidirectional"))
    )
    (net (code "93") (name "unconnected-(J1-Pad31)") (class "Default")
      (node (ref "J1") (pin "31") (pinfunction "31_31") (pintype "bidirectional"))
    )
    (net (code "94") (name "unconnected-(J1-Pad32)") (class "Default")
      (node (ref "J1") (pin "32") (pinfunction "32_32") (pintype "bidirectional"))
    )
    (net (code "95") (name "unconnected-(J1-Pad33)") (class "Default")
      (node (ref "J1") (pin "33") (pinfunction "33_33") (pintype "bidirectional"))
    )
    (net (code "96") (name "unconnected-(J1-Pad34)") (class "Default")
      (node (ref "J1") (pin "34") (pinfunction "34_34") (pintype "bidirectional"))
    )
    (net (code "97") (name "unconnected-(J1-Pad35)") (class "Default")
      (node (ref "J1") (pin "35") (pinfunction "35_35") (pintype "bidirectional"))
    )
    (net (code "98") (name "unconnected-(J1-Pad36)") (class "Default")
      (node (ref "J1") (pin "36") (pinfunction "36_36") (pintype "bidirectional"))
    )
    (net (code "99") (name "unconnected-(J1-Pad37)") (class "Default")
      (node (ref "J1") (pin "37") (pinfunction "37_37") (pintype "bidirectional"))
    )
    (net (code "100") (name "unconnected-(J1-Pad38)") (class "Default")
      (node (ref "J1") (pin "38") (pinfunction "38_38") (pintype "bidirectional"))
    )
    (net (code "101") (name "unconnected-(J1-Pad39)") (class "Default")
      (node (ref "J1") (pin "39") (pinfunction "39_39") (pintype "bidirectional"))
    )
    (net (code "102") (name "unconnected-(J1-Pad40)") (class "Default")
      (node (ref "J1") (pin "40") (pinfunction "40_40") (pintype "bidirectional"))
    )
    (net (code "103") (name "unconnected-(J1-Pad41)") (class "Default")
      (node (ref "J1") (pin "41") (pinfunction "41_41") (pintype "bidirectional"))
    )
    (net (code "104") (name "unconnected-(J1-Pad42)") (class "Default")
      (node (ref "J1") (pin "42") (pinfunction "42_42") (pintype "bidirectional"))
    )
    (net (code "105") (name "unconnected-(J1-Pad43)") (class "Default")
      (node (ref "J1") (pin "43") (pinfunction "43_43") (pintype "bidirectional"))
    )
    (net (code "106") (name "unconnected-(J1-Pad44)") (class "Default")
      (node (ref "J1") (pin "44") (pinfunction "44_44") (pintype "bidirectional"))
    )
    (net (code "107") (name "unconnected-(J1-Pad45)") (class "Default")
      (node (ref "J1") (pin "45") (pinfunction "45_45") (pintype "bidirectional"))
    )
    (net (code "108") (name "unconnected-(J1-Pad46)") (class "Default")
      (node (ref "J1") (pin "46") (pinfunction "46_46") (pintype "bidirectional"))
    )
    (net (code "109") (name "unconnected-(J1-Pad47)") (class "Default")
      (node (ref "J1") (pin "47") (pinfunction "47_47") (pintype "bidirectional"))
    )
    (net (code "110") (name "unconnected-(J1-Pad48)") (class "Default")
      (node (ref "J1") (pin "48") (pinfunction "48_48") (pintype "bidirectional"))
    )
    (net (code "111") (name "unconnected-(J1-Pad53)") (class "Default")
      (node (ref "J1") (pin "53") (pinfunction "53_53") (pintype "bidirectional"))
    )
    (net (code "112") (name "unconnected-(J1-Pad54)") (class "Default")
      (node (ref "J1") (pin "54") (pinfunction "54_54") (pintype "bidirectional"))
    )
    (net (code "113") (name "unconnected-(J1-Pad58)") (class "Default")
      (node (ref "J1") (pin "58") (pinfunction "58_58") (pintype "bidirectional"))
    )
    (net (code "114") (name "unconnected-(J1-Pad59)") (class "Default")
      (node (ref "J1") (pin "59") (pinfunction "59_59") (pintype "bidirectional"))
    )
    (net (code "115") (name "unconnected-(J1-Pad60)") (class "Default")
      (node (ref "J1") (pin "60") (pinfunction "60_60") (pintype "bidirectional"))
    )
    (net (code "116") (name "unconnected-(J1B-8-Pad68)") (class "Default")
      (node (ref "J1") (pin "68") (pinfunction "8_68") (pintype "bidirectional"))
    )
    (net (code "117") (name "unconnected-(J1B-10-Pad70)") (class "Default")
      (node (ref "J1") (pin "70") (pinfunction "10_70") (pintype "bidirectional"))
    )
    (net (code "118") (name "unconnected-(J1B-11-Pad71)") (class "Default")
      (node (ref "J1") (pin "71") (pinfunction "11_71") (pintype "bidirectional"))
    )
    (net (code "119") (name "unconnected-(J1B-14-Pad74)") (class "Default")
      (node (ref "J1") (pin "74") (pinfunction "14_74") (pintype "bidirectional"))
    )
    (net (code "120") (name "unconnected-(J1B-16-Pad76)") (class "Default")
      (node (ref "J1") (pin "76") (pinfunction "16_76") (pintype "bidirectional"))
    )
    (net (code "121") (name "unconnected-(J1B-17-Pad77)") (class "Default")
      (node (ref "J1") (pin "77") (pinfunction "17_77") (pintype "bidirectional"))
    )
    (net (code "122") (name "unconnected-(J1B-20-Pad80)") (class "Default")
      (node (ref "J1") (pin "80") (pinfunction "20_80") (pintype "bidirectional"))
    )
    (net (code "123") (name "unconnected-(J1B-22-Pad82)") (class "Default")
      (node (ref "J1") (pin "82") (pinfunction "22_82") (pintype "bidirectional"))
    )
    (net (code "124") (name "unconnected-(J1B-23-Pad83)") (class "Default")
      (node (ref "J1") (pin "83") (pinfunction "23_83") (pintype "bidirectional"))
    )
    (net (code "125") (name "unconnected-(J1B-26-Pad86)") (class "Default")
      (node (ref "J1") (pin "86") (pinfunction "26_86") (pintype "bidirectional"))
    )
    (net (code "126") (name "unconnected-(J1B-28-Pad88)") (class "Default")
      (node (ref "J1") (pin "88") (pinfunction "28_88") (pintype "bidirectional"))
    )
    (net (code "127") (name "unconnected-(J1B-31-Pad91)") (class "Default")
      (node (ref "J1") (pin "91") (pinfunction "31_91") (pintype "bidirectional"))
    )
    (net (code "128") (name "unconnected-(J1B-32-Pad92)") (class "Default")
      (node (ref "J1") (pin "92") (pinfunction "32_92") (pintype "bidirectional"))
    )
    (net (code "129") (name "unconnected-(J1B-33-Pad93)") (class "Default")
      (node (ref "J1") (pin "93") (pinfunction "33_93") (pintype "bidirectional"))
    )
    (net (code "130") (name "unconnected-(J1B-34-Pad94)") (class "Default")
      (node (ref "J1") (pin "94") (pinfunction "34_94") (pintype "bidirectional"))
    )
    (net (code "131") (name "unconnected-(J1B-37-Pad97)") (class "Default")
      (node (ref "J1") (pin "97") (pinfunction "37_97") (pintype "bidirectional"))
    )
    (net (code "132") (name "unconnected-(J1B-38-Pad98)") (class "Default")
      (node (ref "J1") (pin "98") (pinfunction "38_98") (pintype "bidirectional"))
    )
    (net (code "133") (name "unconnected-(J1B-39-Pad99)") (class "Default")
      (node (ref "J1") (pin "99") (pinfunction "39_99") (pintype "bidirectional"))
    )
    (net (code "134") (name "unconnected-(J1B-40-Pad100)") (class "Default")
      (node (ref "J1") (pin "100") (pinfunction "40_100") (pintype "bidirectional"))
    )
    (net (code "135") (name "unconnected-(J1B-43-Pad103)") (class "Default")
      (node (ref "J1") (pin "103") (pinfunction "43_103") (pintype "bidirectional"))
    )
    (net (code "136") (name "unconnected-(J1B-44-Pad104)") (class "Default")
      (node (ref "J1") (pin "104") (pinfunction "44_104") (pintype "bidirectional"))
    )
    (net (code "137") (name "unconnected-(J1B-45-Pad105)") (class "Default")
      (node (ref "J1") (pin "105") (pinfunction "45_105") (pintype "bidirectional"))
    )
    (net (code "138") (name "unconnected-(J1B-46-Pad106)") (class "Default")
      (node (ref "J1") (pin "106") (pinfunction "46_106") (pintype "bidirectional"))
    )
    (net (code "139") (name "unconnected-(J1B-49-Pad109)") (class "Default")
      (node (ref "J1") (pin "109") (pinfunction "49_109") (pintype "bidirectional"))
    )
    (net (code "140") (name "unconnected-(J1B-50-Pad110)") (class "Default")
      (node (ref "J1") (pin "110") (pinfunction "50_110") (pintype "bidirectional"))
    )
    (net (code "141") (name "unconnected-(J1B-51-Pad111)") (class "Default")
      (node (ref "J1") (pin "111") (pinfunction "51_111") (pintype "bidirectional"))
    )
    (net (code "142") (name "unconnected-(J1B-52-Pad112)") (class "Default")
      (node (ref "J1") (pin "112") (pinfunction "52_112") (pintype "bidirectional"))
    )
    (net (code "143") (name "unconnected-(J1B-56-Pad116)") (class "Default")
      (node (ref "J1") (pin "116") (pinfunction "56_116") (pintype "bidirectional"))
    )
    (net (code "144") (name "unconnected-(J1B-58-Pad118)") (class "Default")
      (node (ref "J1") (pin "118") (pinfunction "58_118") (pintype "bidirectional"))
    )
    (net (code "145") (name "unconnected-(J1C-1-Pad121)") (class "Default")
      (node (ref "J1") (pin "121") (pinfunction "1_121") (pintype "bidirectional"))
    )
    (net (code "146") (name "unconnected-(J1C-2-Pad122)") (class "Default")
      (node (ref "J1") (pin "122") (pinfunction "2_122") (pintype "bidirectional"))
    )
    (net (code "147") (name "unconnected-(J1C-3-Pad123)") (class "Default")
      (node (ref "J1") (pin "123") (pinfunction "3_123") (pintype "bidirectional"))
    )
    (net (code "148") (name "unconnected-(J1C-4-Pad124)") (class "Default")
      (node (ref "J1") (pin "124") (pinfunction "4_124") (pintype "bidirectional"))
    )
    (net (code "149") (name "unconnected-(J1C-7-Pad127)") (class "Default")
      (node (ref "J1") (pin "127") (pinfunction "7_127") (pintype "bidirectional"))
    )
    (net (code "150") (name "unconnected-(J1C-8-Pad128)") (class "Default")
      (node (ref "J1") (pin "128") (pinfunction "8_128") (pintype "bidirectional"))
    )
    (net (code "151") (name "unconnected-(J1C-9-Pad129)") (class "Default")
      (node (ref "J1") (pin "129") (pinfunction "9_129") (pintype "bidirectional"))
    )
    (net (code "152") (name "unconnected-(J1C-10-Pad130)") (class "Default")
      (node (ref "J1") (pin "130") (pinfunction "10_130") (pintype "bidirectional"))
    )
    (net (code "153") (name "unconnected-(J1C-13-Pad133)") (class "Default")
      (node (ref "J1") (pin "133") (pinfunction "13_133") (pintype "bidirectional"))
    )
    (net (code "154") (name "unconnected-(J1C-14-Pad134)") (class "Default")
      (node (ref "J1") (pin "134") (pinfunction "14_134") (pintype "bidirectional"))
    )
    (net (code "155") (name "unconnected-(J1C-15-Pad135)") (class "Default")
      (node (ref "J1") (pin "135") (pinfunction "15_135") (pintype "bidirectional"))
    )
    (net (code "156") (name "unconnected-(J1C-16-Pad136)") (class "Default")
      (node (ref "J1") (pin "136") (pinfunction "16_136") (pintype "bidirectional"))
    )
    (net (code "157") (name "unconnected-(J1C-19-Pad139)") (class "Default")
      (node (ref "J1") (pin "139") (pinfunction "19_139") (pintype "bidirectional"))
    )
    (net (code "158") (name "unconnected-(J1C-20-Pad140)") (class "Default")
      (node (ref "J1") (pin "140") (pinfunction "20_140") (pintype "bidirectional"))
    )
    (net (code "159") (name "unconnected-(J1C-21-Pad141)") (class "Default")
      (node (ref "J1") (pin "141") (pinfunction "21_141") (pintype "bidirectional"))
    )
    (net (code "160") (name "unconnected-(J1C-22-Pad142)") (class "Default")
      (node (ref "J1") (pin "142") (pinfunction "22_142") (pintype "bidirectional"))
    )
    (net (code "161") (name "unconnected-(J1C-25-Pad145)") (class "Default")
      (node (ref "J1") (pin "145") (pinfunction "25_145") (pintype "bidirectional"))
    )
    (net (code "162") (name "unconnected-(J1C-26-Pad146)") (class "Default")
      (node (ref "J1") (pin "146") (pinfunction "26_146") (pintype "bidirectional"))
    )
    (net (code "163") (name "unconnected-(J1C-27-Pad147)") (class "Default")
      (node (ref "J1") (pin "147") (pinfunction "27_147") (pintype "bidirectional"))
    )
    (net (code "164") (name "unconnected-(J1C-28-Pad148)") (class "Default")
      (node (ref "J1") (pin "148") (pinfunction "28_148") (pintype "bidirectional"))
    )
    (net (code "165") (name "unconnected-(J1C-31-Pad151)") (class "Default")
      (node (ref "J1") (pin "151") (pinfunction "31_151") (pintype "bidirectional"))
    )
    (net (code "166") (name "unconnected-(J1C-32-Pad152)") (class "Default")
      (node (ref "J1") (pin "152") (pinfunction "32_152") (pintype "bidirectional"))
    )
    (net (code "167") (name "unconnected-(J1C-33-Pad153)") (class "Default")
      (node (ref "J1") (pin "153") (pinfunction "33_153") (pintype "bidirectional"))
    )
    (net (code "168") (name "unconnected-(J1C-34-Pad154)") (class "Default")
      (node (ref "J1") (pin "154") (pinfunction "34_154") (pintype "bidirectional"))
    )
    (net (code "169") (name "unconnected-(J1C-37-Pad157)") (class "Default")
      (node (ref "J1") (pin "157") (pinfunction "37_157") (pintype "bidirectional"))
    )
    (net (code "170") (name "unconnected-(J1C-38-Pad158)") (class "Default")
      (node (ref "J1") (pin "158") (pinfunction "38_158") (pintype "bidirectional"))
    )
    (net (code "171") (name "unconnected-(J1C-39-Pad159)") (class "Default")
      (node (ref "J1") (pin "159") (pinfunction "39_159") (pintype "bidirectional"))
    )
    (net (code "172") (name "unconnected-(J1C-40-Pad160)") (class "Default")
      (node (ref "J1") (pin "160") (pinfunction "40_160") (pintype "bidirectional"))
    )
    (net (code "173") (name "unconnected-(J1C-43-Pad163)") (class "Default")
      (node (ref "J1") (pin "163") (pinfunction "43_163") (pintype "bidirectional"))
    )
    (net (code "174") (name "unconnected-(J1C-44-Pad164)") (class "Default")
      (node (ref "J1") (pin "164") (pinfunction "44_164") (pintype "bidirectional"))
    )
    (net (code "175") (name "unconnected-(J1C-45-Pad165)") (class "Default")
      (node (ref "J1") (pin "165") (pinfunction "45_165") (pintype "bidirectional"))
    )
    (net (code "176") (name "unconnected-(J1C-46-Pad166)") (class "Default")
      (node (ref "J1") (pin "166") (pinfunction "46_166") (pintype "bidirectional"))
    )
    (net (code "177") (name "unconnected-(J1C-49-Pad169)") (class "Default")
      (node (ref "J1") (pin "169") (pinfunction "49_169") (pintype "bidirectional"))
    )
    (net (code "178") (name "unconnected-(J1C-50-Pad170)") (class "Default")
      (node (ref "J1") (pin "170") (pinfunction "50_170") (pintype "bidirectional"))
    )
    (net (code "179") (name "unconnected-(J1C-51-Pad171)") (class "Default")
      (node (ref "J1") (pin "171") (pinfunction "51_171") (pintype "bidirectional"))
    )
    (net (code "180") (name "unconnected-(J1C-52-Pad172)") (class "Default")
      (node (ref "J1") (pin "172") (pinfunction "52_172") (pintype "bidirectional"))
    )
    (net (code "181") (name "unconnected-(J1C-56-Pad176)") (class "Default")
      (node (ref "J1") (pin "176") (pinfunction "56_176") (pintype "bidirectional"))
    )
    (net (code "182") (name "unconnected-(J1C-58-Pad178)") (class "Default")
      (node (ref "J1") (pin "178") (pinfunction "58_178") (pintype "bidirectional"))
    )
  )
)
